# capstone.net
KiCad netlist of a schematic drawn in EAGLE
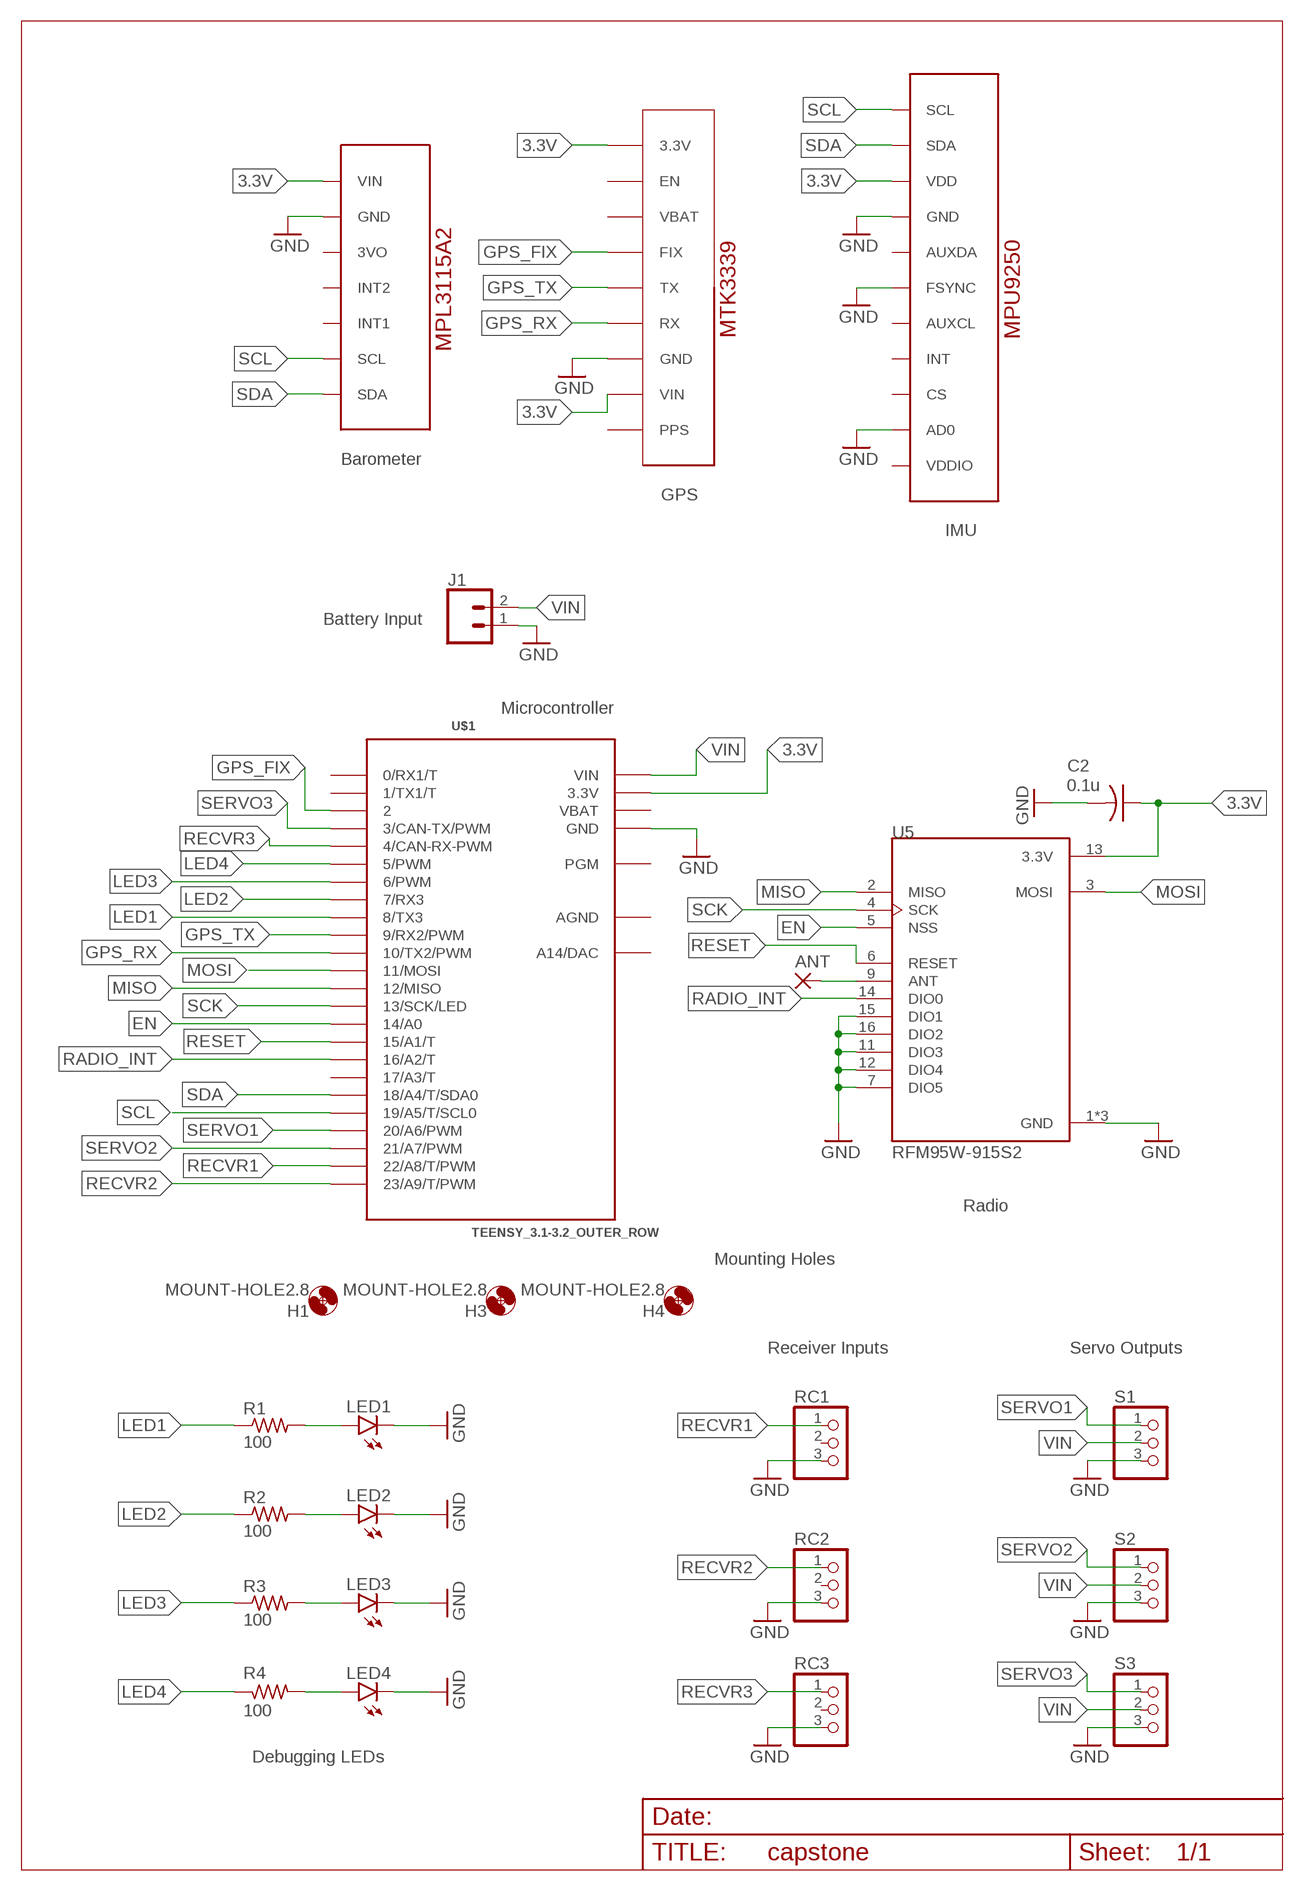
[diagram p0: schematic, sheet 1]

(export (version "E")
  (design (tool "Eeschema 10.0.6"))
  (components
    (comp (ref "ANT")
      (value "2,54/0,9")
      (footprint "eagle-import:2,54_0,9")
      (libsource (lib "eagle-import") (part "2,54/0,9"))
    )
    (comp (ref "C2")
      (value "0.1u")
      (footprint "eagle-import:C1206")
      (libsource (lib "eagle-import") (part "C-USC1206"))
    )
    (comp (ref "H1")
      (value "MOUNT-HOLE2.8")
      (footprint "eagle-import:2,8")
      (libsource (lib "eagle-import") (part "MOUNT-HOLE2.8"))
    )
    (comp (ref "H3")
      (value "MOUNT-HOLE2.8")
      (footprint "eagle-import:2,8")
      (libsource (lib "eagle-import") (part "MOUNT-HOLE2.8"))
    )
    (comp (ref "H4")
      (value "MOUNT-HOLE2.8")
      (footprint "eagle-import:2,8")
      (libsource (lib "eagle-import") (part "MOUNT-HOLE2.8"))
    )
    (comp (ref "J1")
      (value "CONN_025MM")
      (footprint "eagle-import:SCREWTERMINAL-5MM-2")
      (libsource (lib "eagle-import") (part "CONN_025MM"))
    )
    (comp (ref "LED1")
      (value "LEDCHIPLED_1206")
      (footprint "eagle-import:CHIPLED_1206")
      (libsource (lib "eagle-import") (part "LEDCHIPLED_1206"))
    )
    (comp (ref "LED2")
      (value "LEDCHIPLED_1206")
      (footprint "eagle-import:CHIPLED_1206")
      (libsource (lib "eagle-import") (part "LEDCHIPLED_1206"))
    )
    (comp (ref "LED3")
      (value "LEDCHIPLED_1206")
      (footprint "eagle-import:CHIPLED_1206")
      (libsource (lib "eagle-import") (part "LEDCHIPLED_1206"))
    )
    (comp (ref "LED4")
      (value "LEDCHIPLED_1206")
      (footprint "eagle-import:CHIPLED_1206")
      (libsource (lib "eagle-import") (part "LEDCHIPLED_1206"))
    )
    (comp (ref "R1")
      (value "100")
      (footprint "eagle-import:M1206")
      (libsource (lib "eagle-import") (part "R-US_M1206"))
    )
    (comp (ref "R2")
      (value "100")
      (footprint "eagle-import:M1206")
      (libsource (lib "eagle-import") (part "R-US_M1206"))
    )
    (comp (ref "R3")
      (value "100")
      (footprint "eagle-import:M1206")
      (libsource (lib "eagle-import") (part "R-US_M1206"))
    )
    (comp (ref "R4")
      (value "100")
      (footprint "eagle-import:M1206")
      (libsource (lib "eagle-import") (part "R-US_M1206"))
    )
    (comp (ref "RC1")
      (value "PINHD-1X3")
      (footprint "eagle-import:1X03")
      (libsource (lib "eagle-import") (part "PINHD-1X3"))
    )
    (comp (ref "RC2")
      (value "PINHD-1X3")
      (footprint "eagle-import:1X03")
      (libsource (lib "eagle-import") (part "PINHD-1X3"))
    )
    (comp (ref "RC3")
      (value "PINHD-1X3")
      (footprint "eagle-import:1X03")
      (libsource (lib "eagle-import") (part "PINHD-1X3"))
    )
    (comp (ref "S1")
      (value "PINHD-1X3")
      (footprint "eagle-import:1X03")
      (libsource (lib "eagle-import") (part "PINHD-1X3"))
    )
    (comp (ref "S2")
      (value "PINHD-1X3")
      (footprint "eagle-import:1X03")
      (libsource (lib "eagle-import") (part "PINHD-1X3"))
    )
    (comp (ref "S3")
      (value "PINHD-1X3")
      (footprint "eagle-import:1X03")
      (libsource (lib "eagle-import") (part "PINHD-1X3"))
    )
    (comp (ref "U$1")
      (value "TEENSY_3.1-3.2_OUTER_ROW")
      (footprint "eagle-import:TEENSY_3.0-3.2&LC_OUTER_ROW")
      (libsource (lib "eagle-import") (part "TEENSY_3.1-3.2_OUTER_ROW"))
    )
    (comp (ref "U1")
      (value "ADAFRUIT_MPL3115A2_BAROMETER")
      (footprint "eagle-import:ADAFRUIT_MPL3115A2_BAROMETER")
      (libsource (lib "eagle-import") (part "ADAFRUIT_MPL3115A2_BAROMETER"))
    )
    (comp (ref "U2")
      (value "ADAFRUIT_MTK3339_GPS")
      (footprint "eagle-import:ADAFRUIT_MTK3339_GPS")
      (libsource (lib "eagle-import") (part "ADAFRUIT_MTK3339_GPS"))
    )
    (comp (ref "U4")
      (value "SPARKFUN_MPU9250_IMU")
      (footprint "eagle-import:SPARKFUN_MPU9250_IMU")
      (libsource (lib "eagle-import") (part "SPARKFUN_MPU9250_IMU"))
    )
    (comp (ref "U5")
      (value "RFM95W-915S2")
      (footprint "eagle-import:XCVR_RFM95W-915S2")
      (fields (field (name "DIGI-KEY_PART_NUMBER") "RFM95W-915S2-ND") (field (name "MF") "RF Solutions"))
      (libsource (lib "eagle-import") (part "RFM95W-915S2"))
    )
  )
  (nets
    (net (code "1") (name "/AGND") (class "Default")
      (node (ref "U$1") (pin "AGND") (pinfunction "AGND_AGND") (pintype "power_in"))
    )
    (net (code "2") (name "/VBAT") (class "Default")
      (node (ref "U$1") (pin "VBAT") (pinfunction "VBAT_VBAT") (pintype "power_in"))
    )
    (net (code "3") (name "3.3V") (class "Default")
      (node (ref "C2") (pin "1") (pinfunction "1_1") (pintype "passive"))
      (node (ref "U$1") (pin "3.3V") (pinfunction "3.3V_3.3V") (pintype "power_in"))
      (node (ref "U$1") (pin "3.3V1") (pinfunction "3.3V_3.3V1") (pintype "power_in"))
      (node (ref "U1") (pin "VIN") (pinfunction "VIN_VIN") (pintype "bidirectional"))
      (node (ref "U2") (pin "3.3V") (pinfunction "3.3V_3.3V") (pintype "bidirectional"))
      (node (ref "U2") (pin "VIN") (pinfunction "VIN_VIN") (pintype "bidirectional"))
      (node (ref "U4") (pin "VDD") (pinfunction "VDD_VDD") (pintype "bidirectional"))
      (node (ref "U5") (pin "13") (pinfunction "3.3V_13") (pintype "power_in"))
    )
    (net (code "4") (name "EN") (class "Default")
      (node (ref "U$1") (pin "14/A0") (pinfunction "14/A0_14/A0") (pintype "bidirectional"))
      (node (ref "U5") (pin "5") (pinfunction "NSS_5") (pintype "input"))
    )
    (net (code "5") (name "GND") (class "Default")
      (node (ref "C2") (pin "2") (pinfunction "2_2") (pintype "passive"))
      (node (ref "J1") (pin "1") (pinfunction "1_1") (pintype "passive"))
      (node (ref "LED1") (pin "C") (pinfunction "C_C") (pintype "passive"))
      (node (ref "LED2") (pin "C") (pinfunction "C_C") (pintype "passive"))
      (node (ref "LED3") (pin "C") (pinfunction "C_C") (pintype "passive"))
      (node (ref "LED4") (pin "C") (pinfunction "C_C") (pintype "passive"))
      (node (ref "RC1") (pin "3") (pinfunction "3_3") (pintype "passive"))
      (node (ref "RC2") (pin "3") (pinfunction "3_3") (pintype "passive"))
      (node (ref "RC3") (pin "3") (pinfunction "3_3") (pintype "passive"))
      (node (ref "S1") (pin "3") (pinfunction "3_3") (pintype "passive"))
      (node (ref "S2") (pin "3") (pinfunction "3_3") (pintype "passive"))
      (node (ref "S3") (pin "3") (pinfunction "3_3") (pintype "passive"))
      (node (ref "U$1") (pin "GND") (pinfunction "GND_GND") (pintype "power_in"))
      (node (ref "U$1") (pin "GND1") (pinfunction "GND_GND1") (pintype "power_in"))
      (node (ref "U1") (pin "GND") (pinfunction "GND_GND") (pintype "bidirectional"))
      (node (ref "U2") (pin "GND") (pinfunction "GND_GND") (pintype "bidirectional"))
      (node (ref "U4") (pin "AD0") (pinfunction "AD0_AD0") (pintype "bidirectional"))
      (node (ref "U4") (pin "FSYNC") (pinfunction "FSYNC_FSYNC") (pintype "bidirectional"))
      (node (ref "U4") (pin "GND") (pinfunction "GND_GND") (pintype "bidirectional"))
      (node (ref "U5") (pin "1") (pinfunction "GND_1") (pintype "power_in"))
      (node (ref "U5") (pin "10") (pinfunction "GND_10") (pintype "power_in"))
      (node (ref "U5") (pin "11") (pinfunction "DIO3_11") (pintype "bidirectional"))
      (node (ref "U5") (pin "12") (pinfunction "DIO4_12") (pintype "bidirectional"))
      (node (ref "U5") (pin "15") (pinfunction "DIO1_15") (pintype "bidirectional"))
      (node (ref "U5") (pin "16") (pinfunction "DIO2_16") (pintype "bidirectional"))
      (node (ref "U5") (pin "7") (pinfunction "DIO5_7") (pintype "bidirectional"))
      (node (ref "U5") (pin "8") (pinfunction "GND_8") (pintype "power_in"))
    )
    (net (code "6") (name "GPS_FIX") (class "Default")
      (node (ref "U$1") (pin "2") (pinfunction "2_2") (pintype "bidirectional"))
      (node (ref "U2") (pin "FIX") (pinfunction "FIX_FIX") (pintype "bidirectional"))
    )
    (net (code "7") (name "GPS_RX") (class "Default")
      (node (ref "U$1") (pin "10") (pinfunction "10/TX2/PWM_10") (pintype "bidirectional"))
      (node (ref "U2") (pin "RX") (pinfunction "RX_RX") (pintype "bidirectional"))
    )
    (net (code "8") (name "GPS_TX") (class "Default")
      (node (ref "U$1") (pin "9") (pinfunction "9/RX2/PWM_9") (pintype "bidirectional"))
      (node (ref "U2") (pin "TX") (pinfunction "TX_TX") (pintype "bidirectional"))
    )
    (net (code "9") (name "LED1") (class "Default")
      (node (ref "R1") (pin "1") (pinfunction "1_1") (pintype "passive"))
      (node (ref "U$1") (pin "8") (pinfunction "8/TX3_8") (pintype "bidirectional"))
    )
    (net (code "10") (name "LED2") (class "Default")
      (node (ref "R2") (pin "1") (pinfunction "1_1") (pintype "passive"))
      (node (ref "U$1") (pin "7") (pinfunction "7/RX3_7") (pintype "bidirectional"))
    )
    (net (code "11") (name "LED3") (class "Default")
      (node (ref "R3") (pin "1") (pinfunction "1_1") (pintype "passive"))
      (node (ref "U$1") (pin "6") (pinfunction "6/PWM_6") (pintype "bidirectional"))
    )
    (net (code "12") (name "LED4") (class "Default")
      (node (ref "R4") (pin "1") (pinfunction "1_1") (pintype "passive"))
      (node (ref "U$1") (pin "5") (pinfunction "5/PWM_5") (pintype "bidirectional"))
    )
    (net (code "13") (name "MISO") (class "Default")
      (node (ref "U$1") (pin "12") (pinfunction "12/MISO_12") (pintype "bidirectional"))
      (node (ref "U5") (pin "2") (pinfunction "MISO_2") (pintype "input"))
    )
    (net (code "14") (name "MOSI") (class "Default")
      (node (ref "U$1") (pin "11") (pinfunction "11/MOSI_11") (pintype "bidirectional"))
      (node (ref "U5") (pin "3") (pinfunction "MOSI_3") (pintype "output"))
    )
    (net (code "15") (name "Net-(ANT-P)") (class "Default")
      (node (ref "ANT") (pin "1") (pinfunction "P_1") (pintype "passive"))
      (node (ref "U5") (pin "9") (pinfunction "ANT_9") (pintype "bidirectional"))
    )
    (net (code "16") (name "Net-(LED1-PadA)") (class "Default")
      (node (ref "LED1") (pin "A") (pinfunction "A_A") (pintype "passive"))
      (node (ref "R1") (pin "2") (pinfunction "2_2") (pintype "passive"))
    )
    (net (code "17") (name "Net-(LED2-PadA)") (class "Default")
      (node (ref "LED2") (pin "A") (pinfunction "A_A") (pintype "passive"))
      (node (ref "R2") (pin "2") (pinfunction "2_2") (pintype "passive"))
    )
    (net (code "18") (name "Net-(LED3-PadA)") (class "Default")
      (node (ref "LED3") (pin "A") (pinfunction "A_A") (pintype "passive"))
      (node (ref "R3") (pin "2") (pinfunction "2_2") (pintype "passive"))
    )
    (net (code "19") (name "Net-(LED4-PadA)") (class "Default")
      (node (ref "LED4") (pin "A") (pinfunction "A_A") (pintype "passive"))
      (node (ref "R4") (pin "2") (pinfunction "2_2") (pintype "passive"))
    )
    (net (code "20") (name "RADIO_INT") (class "Default")
      (node (ref "U$1") (pin "16/A2") (pinfunction "16/A2/T_16/A2") (pintype "bidirectional"))
      (node (ref "U5") (pin "14") (pinfunction "DIO0_14") (pintype "bidirectional"))
    )
    (net (code "21") (name "RECVR1") (class "Default")
      (node (ref "RC1") (pin "1") (pinfunction "1_1") (pintype "passive"))
      (node (ref "U$1") (pin "22/A8") (pinfunction "22/A8/T/PWM_22/A8") (pintype "bidirectional"))
    )
    (net (code "22") (name "RECVR2") (class "Default")
      (node (ref "RC2") (pin "1") (pinfunction "1_1") (pintype "passive"))
      (node (ref "U$1") (pin "23/A9") (pinfunction "23/A9/T/PWM_23/A9") (pintype "bidirectional"))
    )
    (net (code "23") (name "RECVR3") (class "Default")
      (node (ref "RC3") (pin "1") (pinfunction "1_1") (pintype "passive"))
      (node (ref "U$1") (pin "4") (pinfunction "4/CAN-RX-PWM_4") (pintype "bidirectional"))
    )
    (net (code "24") (name "RESET") (class "Default")
      (node (ref "U$1") (pin "15/A1") (pinfunction "15/A1/T_15/A1") (pintype "bidirectional"))
      (node (ref "U5") (pin "6") (pinfunction "RESET_6") (pintype "bidirectional"))
    )
    (net (code "25") (name "SCK") (class "Default")
      (node (ref "U$1") (pin "13") (pinfunction "13/SCK/LED_13") (pintype "bidirectional"))
      (node (ref "U5") (pin "4") (pinfunction "SCK_4") (pintype "input"))
    )
    (net (code "26") (name "SCL") (class "Default")
      (node (ref "U$1") (pin "19/A5") (pinfunction "19/A5/T/SCL0_19/A5") (pintype "bidirectional"))
      (node (ref "U1") (pin "SCL") (pinfunction "SCL_SCL") (pintype "bidirectional"))
      (node (ref "U4") (pin "SCL") (pinfunction "SCL_SCL") (pintype "bidirectional"))
    )
    (net (code "27") (name "SDA") (class "Default")
      (node (ref "U$1") (pin "18/A4") (pinfunction "18/A4/T/SDA0_18/A4") (pintype "bidirectional"))
      (node (ref "U1") (pin "SDA") (pinfunction "SDA_SDA") (pintype "bidirectional"))
      (node (ref "U4") (pin "SDA") (pinfunction "SDA_SDA") (pintype "bidirectional"))
    )
    (net (code "28") (name "SERVO1") (class "Default")
      (node (ref "S1") (pin "1") (pinfunction "1_1") (pintype "passive"))
      (node (ref "U$1") (pin "20/A6") (pinfunction "20/A6/PWM_20/A6") (pintype "bidirectional"))
    )
    (net (code "29") (name "SERVO2") (class "Default")
      (node (ref "S2") (pin "1") (pinfunction "1_1") (pintype "passive"))
      (node (ref "U$1") (pin "21/A7") (pinfunction "21/A7/PWM_21/A7") (pintype "bidirectional"))
    )
    (net (code "30") (name "SERVO3") (class "Default")
      (node (ref "S3") (pin "1") (pinfunction "1_1") (pintype "passive"))
      (node (ref "U$1") (pin "3") (pinfunction "3/CAN-TX/PWM_3") (pintype "bidirectional"))
    )
    (net (code "31") (name "VIN") (class "Default")
      (node (ref "J1") (pin "2") (pinfunction "2_2") (pintype "passive"))
      (node (ref "S1") (pin "2") (pinfunction "2_2") (pintype "passive"))
      (node (ref "S2") (pin "2") (pinfunction "2_2") (pintype "passive"))
      (node (ref "S3") (pin "2") (pinfunction "2_2") (pintype "passive"))
      (node (ref "U$1") (pin "VIN") (pinfunction "VIN_VIN") (pintype "power_in"))
    )
    (net (code "32") (name "unconnected-(RC1-Pad2)") (class "Default")
      (node (ref "RC1") (pin "2") (pinfunction "2_2") (pintype "passive"))
    )
    (net (code "33") (name "unconnected-(RC2-Pad2)") (class "Default")
      (node (ref "RC2") (pin "2") (pinfunction "2_2") (pintype "passive"))
    )
    (net (code "34") (name "unconnected-(RC3-Pad2)") (class "Default")
      (node (ref "RC3") (pin "2") (pinfunction "2_2") (pintype "passive"))
    )
    (net (code "35") (name "unconnected-(U$1-0{slash}RX1{slash}T-Pad0)") (class "Default")
      (node (ref "U$1") (pin "0") (pinfunction "0/RX1/T_0") (pintype "bidirectional"))
    )
    (net (code "36") (name "unconnected-(U$1-1{slash}TX1{slash}T-Pad1)") (class "Default")
      (node (ref "U$1") (pin "1") (pinfunction "1/TX1/T_1") (pintype "bidirectional"))
    )
    (net (code "37") (name "unconnected-(U$1-17{slash}A3{slash}T-Pad17{slash}A3)") (class "Default")
      (node (ref "U$1") (pin "17/A3") (pinfunction "17/A3/T_17/A3") (pintype "bidirectional"))
    )
    (net (code "38") (name "unconnected-(U$1-A14{slash}DAC-PadRESET{slash}DAC)") (class "Default")
      (node (ref "U$1") (pin "RESET/DAC") (pinfunction "A14/DAC_RESET/DAC") (pintype "bidirectional"))
    )
    (net (code "39") (name "unconnected-(U$1-PadPGM)") (class "Default")
      (node (ref "U$1") (pin "PGM") (pinfunction "PGM_PGM") (pintype "bidirectional"))
    )
    (net (code "40") (name "unconnected-(U1-Pad3VO)") (class "Default")
      (node (ref "U1") (pin "3VO") (pinfunction "3VO_3VO") (pintype "bidirectional"))
    )
    (net (code "41") (name "unconnected-(U1-PadINT1)") (class "Default")
      (node (ref "U1") (pin "INT1") (pinfunction "INT1_INT1") (pintype "bidirectional"))
    )
    (net (code "42") (name "unconnected-(U1-PadINT2)") (class "Default")
      (node (ref "U1") (pin "INT2") (pinfunction "INT2_INT2") (pintype "bidirectional"))
    )
    (net (code "43") (name "unconnected-(U2-PadEN)") (class "Default")
      (node (ref "U2") (pin "EN") (pinfunction "EN_EN") (pintype "bidirectional"))
    )
    (net (code "44") (name "unconnected-(U2-PadPPS)") (class "Default")
      (node (ref "U2") (pin "PPS") (pinfunction "PPS_PPS") (pintype "bidirectional"))
    )
    (net (code "45") (name "unconnected-(U2-PadVBAT)") (class "Default")
      (node (ref "U2") (pin "VBAT") (pinfunction "VBAT_VBAT") (pintype "bidirectional"))
    )
    (net (code "46") (name "unconnected-(U4-PadAUXCL)") (class "Default")
      (node (ref "U4") (pin "AUXCL") (pinfunction "AUXCL_AUXCL") (pintype "bidirectional"))
    )
    (net (code "47") (name "unconnected-(U4-PadAUXDA)") (class "Default")
      (node (ref "U4") (pin "AUXDA") (pinfunction "AUXDA_AUXDA") (pintype "bidirectional"))
    )
    (net (code "48") (name "unconnected-(U4-PadCS)") (class "Default")
      (node (ref "U4") (pin "CS") (pinfunction "CS_CS") (pintype "bidirectional"))
    )
    (net (code "49") (name "unconnected-(U4-PadINT)") (class "Default")
      (node (ref "U4") (pin "INT") (pinfunction "INT_INT") (pintype "bidirectional"))
    )
    (net (code "50") (name "unconnected-(U4-PadVDDIO)") (class "Default")
      (node (ref "U4") (pin "VDDIO") (pinfunction "VDDIO_VDDIO") (pintype "bidirectional"))
    )
  )
)
